# trololo.net
KiCad netlist of a schematic drawn in EAGLE
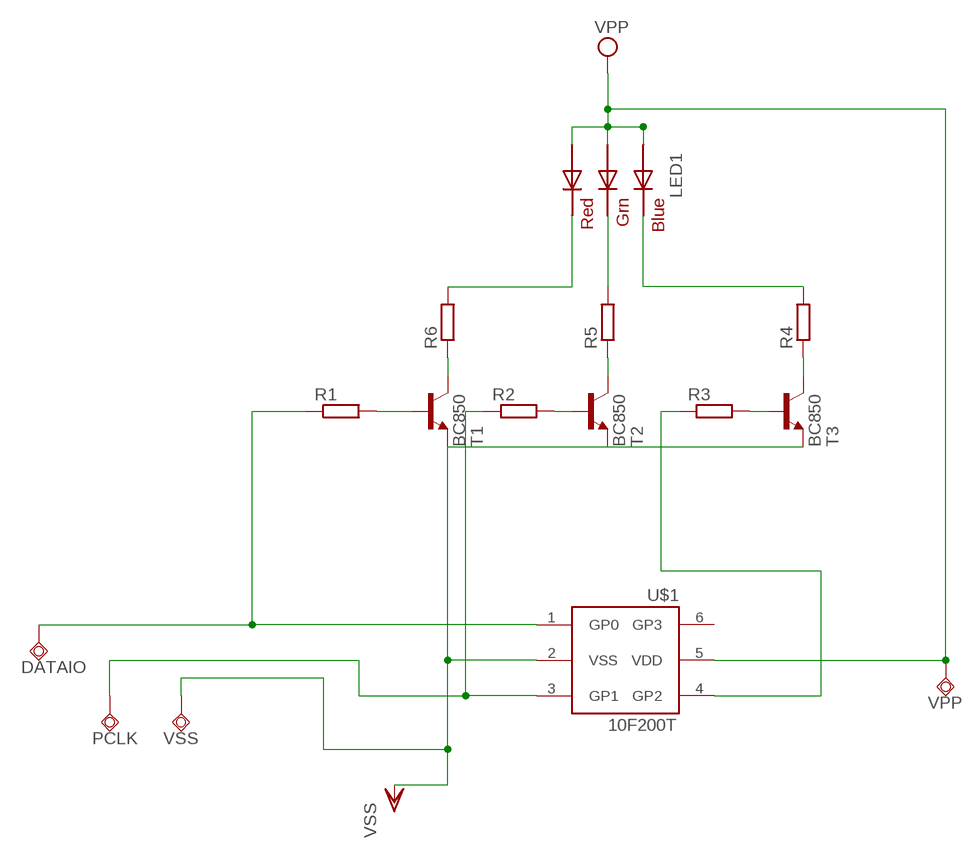
[diagram p0: schematic, sheet 1]

(export (version "E")
  (design (tool "Eeschema 10.0.6"))
  (components
    (comp (ref "DATAIO")
      (value "TPSQPAD1-20Y")
      (footprint "eagle-import:P1-20Y")
      (libsource (lib "eagle-import") (part "TPSQPAD1-20Y"))
    )
    (comp (ref "LED1")
      (value "RGBLED5050")
      (footprint "eagle-import:RGBLED5050")
      (libsource (lib "eagle-import") (part "RGBLED5050"))
    )
    (comp (ref "PCLK")
      (value "TPSQPAD1-20Y")
      (footprint "eagle-import:P1-20Y")
      (libsource (lib "eagle-import") (part "TPSQPAD1-20Y"))
    )
    (comp (ref "R1")
      (value "R-EU_R0805")
      (footprint "eagle-import:R0805")
      (libsource (lib "eagle-import") (part "R-EU_R0805"))
    )
    (comp (ref "R2")
      (value "R-EU_R0805")
      (footprint "eagle-import:R0805")
      (libsource (lib "eagle-import") (part "R-EU_R0805"))
    )
    (comp (ref "R3")
      (value "R-EU_R0805")
      (footprint "eagle-import:R0805")
      (libsource (lib "eagle-import") (part "R-EU_R0805"))
    )
    (comp (ref "R4")
      (value "R-EU_R0805")
      (footprint "eagle-import:R0805")
      (libsource (lib "eagle-import") (part "R-EU_R0805"))
    )
    (comp (ref "R5")
      (value "R-EU_R0805")
      (footprint "eagle-import:R0805")
      (libsource (lib "eagle-import") (part "R-EU_R0805"))
    )
    (comp (ref "R6")
      (value "R-EU_R0805")
      (footprint "eagle-import:R0805")
      (libsource (lib "eagle-import") (part "R-EU_R0805"))
    )
    (comp (ref "T1")
      (value "BC850")
      (footprint "eagle-import:SOT23")
      (libsource (lib "eagle-import") (part "BC850"))
    )
    (comp (ref "T2")
      (value "BC850")
      (footprint "eagle-import:SOT23")
      (libsource (lib "eagle-import") (part "BC850"))
    )
    (comp (ref "T3")
      (value "BC850")
      (footprint "eagle-import:SOT23")
      (libsource (lib "eagle-import") (part "BC850"))
    )
    (comp (ref "U$1")
      (value "10F200T")
      (footprint "eagle-import:SOT23-6")
      (libsource (lib "eagle-import") (part "10F200T"))
    )
    (comp (ref "VPP")
      (value "TPSQPAD1-20Y")
      (footprint "eagle-import:P1-20Y")
      (libsource (lib "eagle-import") (part "TPSQPAD1-20Y"))
    )
    (comp (ref "VSS")
      (value "TPSQPAD1-20Y")
      (footprint "eagle-import:P1-20Y")
      (libsource (lib "eagle-import") (part "TPSQPAD1-20Y"))
    )
  )
  (nets
    (net (code "1") (name "Net-(LED1-BLUE_C)") (class "Default")
      (node (ref "LED1") (pin "4") (pinfunction "BLUE_C_4") (pintype "bidirectional"))
      (node (ref "R4") (pin "2") (pinfunction "2_2") (pintype "passive"))
    )
    (net (code "2") (name "Net-(LED1-GREEN_C)") (class "Default")
      (node (ref "LED1") (pin "6") (pinfunction "GREEN_C_6") (pintype "bidirectional"))
      (node (ref "R5") (pin "2") (pinfunction "2_2") (pintype "passive"))
    )
    (net (code "3") (name "Net-(LED1-RED_C)") (class "Default")
      (node (ref "LED1") (pin "5") (pinfunction "RED_C_5") (pintype "bidirectional"))
      (node (ref "R6") (pin "2") (pinfunction "2_2") (pintype "passive"))
    )
    (net (code "4") (name "Net-(T1-B)") (class "Default")
      (node (ref "R1") (pin "2") (pinfunction "2_2") (pintype "passive"))
      (node (ref "T1") (pin "1") (pinfunction "B_1") (pintype "passive"))
    )
    (net (code "5") (name "Net-(T1-C)") (class "Default")
      (node (ref "R6") (pin "1") (pinfunction "1_1") (pintype "passive"))
      (node (ref "T1") (pin "3") (pinfunction "C_3") (pintype "passive"))
    )
    (net (code "6") (name "Net-(T2-B)") (class "Default")
      (node (ref "R2") (pin "2") (pinfunction "2_2") (pintype "passive"))
      (node (ref "T2") (pin "1") (pinfunction "B_1") (pintype "passive"))
    )
    (net (code "7") (name "Net-(T2-C)") (class "Default")
      (node (ref "R5") (pin "1") (pinfunction "1_1") (pintype "passive"))
      (node (ref "T2") (pin "3") (pinfunction "C_3") (pintype "passive"))
    )
    (net (code "8") (name "Net-(T3-B)") (class "Default")
      (node (ref "R3") (pin "2") (pinfunction "2_2") (pintype "passive"))
      (node (ref "T3") (pin "1") (pinfunction "B_1") (pintype "passive"))
    )
    (net (code "9") (name "Net-(T3-C)") (class "Default")
      (node (ref "R4") (pin "1") (pinfunction "1_1") (pintype "passive"))
      (node (ref "T3") (pin "3") (pinfunction "C_3") (pintype "passive"))
    )
    (net (code "10") (name "Net-(U$1-GP0)") (class "Default")
      (node (ref "DATAIO") (pin "TP") (pinfunction "TP_TP") (pintype "input"))
      (node (ref "R1") (pin "1") (pinfunction "1_1") (pintype "passive"))
      (node (ref "U$1") (pin "1") (pinfunction "GP0_1") (pintype "bidirectional"))
    )
    (net (code "11") (name "Net-(U$1-GP1)") (class "Default")
      (node (ref "PCLK") (pin "TP") (pinfunction "TP_TP") (pintype "input"))
      (node (ref "R2") (pin "1") (pinfunction "1_1") (pintype "passive"))
      (node (ref "U$1") (pin "3") (pinfunction "GP1_3") (pintype "bidirectional"))
    )
    (net (code "12") (name "Net-(U$1-GP2)") (class "Default")
      (node (ref "R3") (pin "1") (pinfunction "1_1") (pintype "passive"))
      (node (ref "U$1") (pin "4") (pinfunction "GP2_4") (pintype "bidirectional"))
    )
    (net (code "13") (name "VPP") (class "Default")
      (node (ref "LED1") (pin "1") (pinfunction "GREEN_A_1") (pintype "bidirectional"))
      (node (ref "LED1") (pin "2") (pinfunction "RED_A_2") (pintype "bidirectional"))
      (node (ref "LED1") (pin "3") (pinfunction "BLUE_A_3") (pintype "bidirectional"))
      (node (ref "U$1") (pin "5") (pinfunction "VDD_5") (pintype "power_in"))
      (node (ref "VPP") (pin "TP") (pinfunction "TP_TP") (pintype "input"))
    )
    (net (code "14") (name "VSS") (class "Default")
      (node (ref "T1") (pin "2") (pinfunction "E_2") (pintype "passive"))
      (node (ref "T2") (pin "2") (pinfunction "E_2") (pintype "passive"))
      (node (ref "T3") (pin "2") (pinfunction "E_2") (pintype "passive"))
      (node (ref "U$1") (pin "2") (pinfunction "VSS_2") (pintype "power_in"))
      (node (ref "VSS") (pin "TP") (pinfunction "TP_TP") (pintype "input"))
    )
    (net (code "15") (name "unconnected-(U$1-GP3-Pad6)") (class "Default")
      (node (ref "U$1") (pin "6") (pinfunction "GP3_6") (pintype "bidirectional"))
    )
  )
)
